# STM32F030F4P6.net
KiCad netlist of a schematic drawn in EAGLE
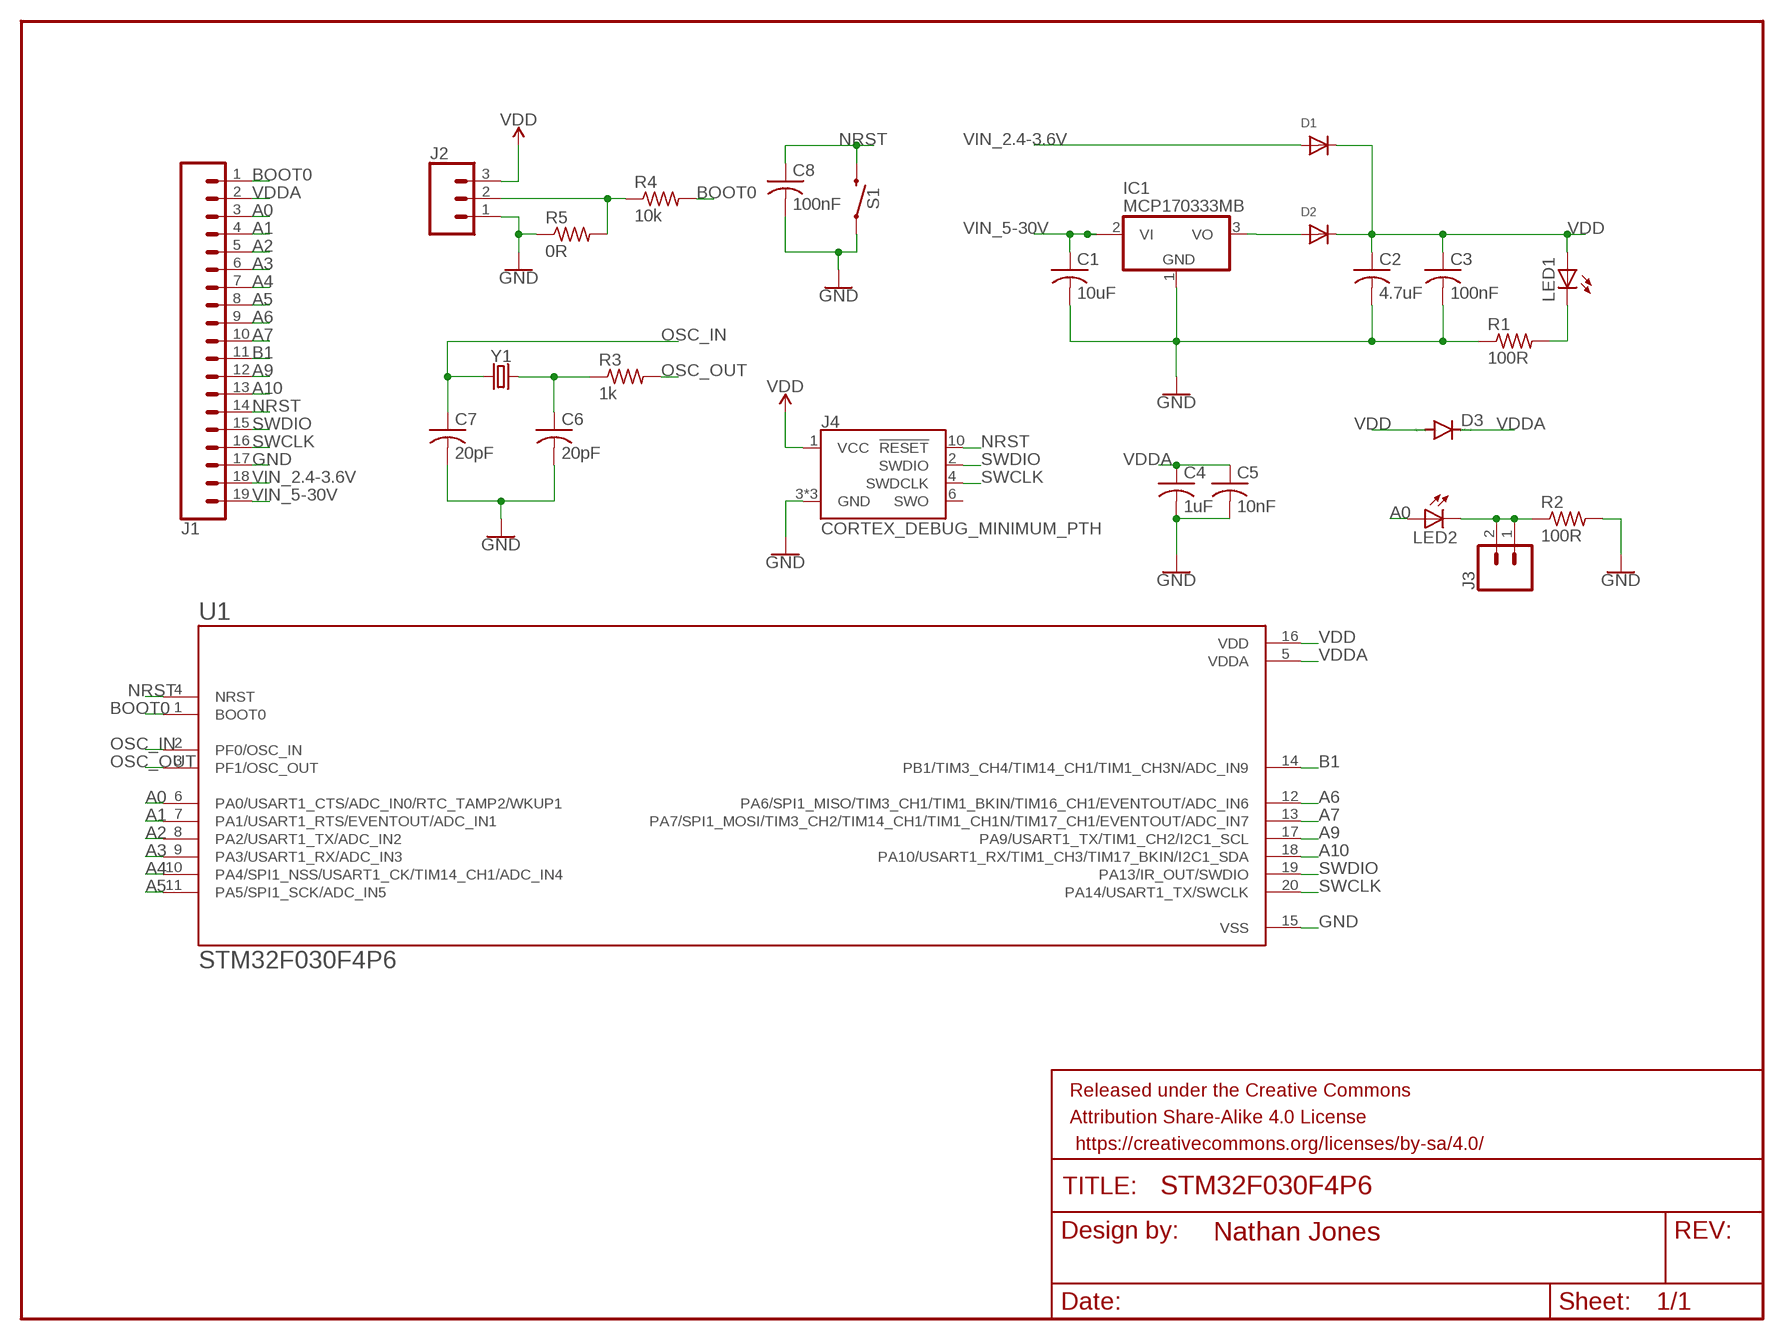
[diagram p0: schematic, sheet 1]

(export (version "E")
  (design (tool "Eeschema 10.0.6"))
  (components
    (comp (ref "C1")
      (value "10uF")
      (footprint "eagle-import:C0603")
      (libsource (lib "eagle-import") (part "C-USC0603"))
    )
    (comp (ref "C2")
      (value "4.7uF")
      (footprint "eagle-import:C0603")
      (libsource (lib "eagle-import") (part "C-USC0603"))
    )
    (comp (ref "C3")
      (value "100nF")
      (footprint "eagle-import:C0603")
      (libsource (lib "eagle-import") (part "C-USC0603"))
    )
    (comp (ref "C4")
      (value "1uF")
      (footprint "eagle-import:C0603")
      (libsource (lib "eagle-import") (part "C-USC0603"))
    )
    (comp (ref "C5")
      (value "10nF")
      (footprint "eagle-import:C0603")
      (libsource (lib "eagle-import") (part "C-USC0603"))
    )
    (comp (ref "C6")
      (value "20pF")
      (footprint "eagle-import:C0603")
      (libsource (lib "eagle-import") (part "C-USC0603"))
    )
    (comp (ref "C7")
      (value "20pF")
      (footprint "eagle-import:C0603")
      (libsource (lib "eagle-import") (part "C-USC0603"))
    )
    (comp (ref "C8")
      (value "100nF")
      (footprint "eagle-import:C0603")
      (libsource (lib "eagle-import") (part "C-USC0603"))
    )
    (comp (ref "D1")
      (value "DIODESOD-123")
      (footprint "eagle-import:SOD-123")
      (libsource (lib "eagle-import") (part "DIODESOD-123"))
    )
    (comp (ref "D2")
      (value "DIODESOD-123")
      (footprint "eagle-import:SOD-123")
      (libsource (lib "eagle-import") (part "DIODESOD-123"))
    )
    (comp (ref "D3")
      (value "DIODE-DO-214AC")
      (footprint "eagle-import:DO-214AC")
      (libsource (lib "eagle-import") (part "DIODE-DO-214AC"))
    )
    (comp (ref "FRAME2")
      (value "FRAME-LETTERNO_PACKAGE")
      (footprint "eagle-import:DUMMY")
      (fields (field (name "DESIGNER") "Nathan Jones") (field (name "DESIGNER_1") "Nathan Jones"))
      (libsource (lib "eagle-import") (part "FRAME-LETTERNO_PACKAGE"))
    )
    (comp (ref "IC1")
      (value "MCP170333MB")
      (footprint "eagle-import:SOT89")
      (libsource (lib "eagle-import") (part "MCP1703MB33"))
    )
    (comp (ref "J1")
      (value "CONN_19")
      (footprint "eagle-import:1X19")
      (libsource (lib "eagle-import") (part "CONN_19"))
    )
    (comp (ref "J2")
      (value "455-1750-1-ND")
      (footprint "eagle-import:1X03")
      (libsource (lib "eagle-import") (part "CONN_03"))
    )
    (comp (ref "J3")
      (value "CONN_02")
      (footprint "eagle-import:1X02")
      (libsource (lib "eagle-import") (part "CONN_02"))
    )
    (comp (ref "J4")
      (value "CORTEX_DEBUG_MINIMUM_PTH")
      (footprint "eagle-import:2X5-PTH-1.27MM")
      (libsource (lib "eagle-import") (part "CORTEX_DEBUG_MINIMUM_PTH"))
    )
    (comp (ref "LED1")
      (value "LEDCHIPLED_0603")
      (footprint "eagle-import:CHIPLED_0603")
      (libsource (lib "eagle-import") (part "LEDCHIPLED_0603"))
    )
    (comp (ref "LED2")
      (value "LEDCHIPLED_0603")
      (footprint "eagle-import:CHIPLED_0603")
      (libsource (lib "eagle-import") (part "LEDCHIPLED_0603"))
    )
    (comp (ref "R1")
      (value "100R")
      (footprint "eagle-import:R0603")
      (libsource (lib "eagle-import") (part "R-US_R0603"))
    )
    (comp (ref "R2")
      (value "100R")
      (footprint "eagle-import:R0603")
      (libsource (lib "eagle-import") (part "R-US_R0603"))
    )
    (comp (ref "R3")
      (value "1k")
      (footprint "eagle-import:R0603")
      (libsource (lib "eagle-import") (part "R-US_R0603"))
    )
    (comp (ref "R4")
      (value "10k")
      (footprint "eagle-import:R0603")
      (libsource (lib "eagle-import") (part "R-US_R0603"))
    )
    (comp (ref "R5")
      (value "0R")
      (footprint "eagle-import:R0603")
      (libsource (lib "eagle-import") (part "R-US_R0603"))
    )
    (comp (ref "S1")
      (value "MOMENTARY-SWITCH-SPST-SMD-5.2-REDUNDANT")
      (footprint "eagle-import:TACTILE_SWITCH_SMD_5.2MM")
      (libsource (lib "eagle-import") (part "MOMENTARY-SWITCH-SPST-SMD-5.2-REDUNDANT"))
    )
    (comp (ref "U1")
      (value "STM32F030F4P6")
      (footprint "eagle-import:SOP65P640X120-20N")
      (fields (field (name "DIGI-KEY_PART_NUMBER") "497-14044-5-ND") (field (name "MF") "STMicroelectronics"))
      (libsource (lib "eagle-import") (part "STM32F030F4P6"))
    )
    (comp (ref "Y1")
      (value "CRYSTALSMD-5X3.2-2PAD")
      (footprint "eagle-import:CRYSTAL-SMD-5X3.2-2PAD")
      (libsource (lib "eagle-import") (part "CRYSTALSMD-5X3.2-2PAD"))
    )
  )
  (nets
    (net (code "1") (name "/A0") (class "Default")
      (node (ref "J1") (pin "3") (pinfunction "3_3") (pintype "passive"))
      (node (ref "LED2") (pin "A") (pinfunction "A_A") (pintype "passive"))
      (node (ref "U1") (pin "6") (pinfunction "PA0/USART1_CTS/ADC_IN0/RTC_TAMP2/WKUP1_6") (pintype "bidirectional"))
    )
    (net (code "2") (name "/A1") (class "Default")
      (node (ref "J1") (pin "4") (pinfunction "4_4") (pintype "passive"))
      (node (ref "U1") (pin "7") (pinfunction "PA1/USART1_RTS/EVENTOUT/ADC_IN1_7") (pintype "bidirectional"))
    )
    (net (code "3") (name "/A2") (class "Default")
      (node (ref "J1") (pin "5") (pinfunction "5_5") (pintype "passive"))
      (node (ref "U1") (pin "8") (pinfunction "PA2/USART1_TX/ADC_IN2_8") (pintype "bidirectional"))
    )
    (net (code "4") (name "/A3") (class "Default")
      (node (ref "J1") (pin "6") (pinfunction "6_6") (pintype "passive"))
      (node (ref "U1") (pin "9") (pinfunction "PA3/USART1_RX/ADC_IN3_9") (pintype "bidirectional"))
    )
    (net (code "5") (name "/A4") (class "Default")
      (node (ref "J1") (pin "7") (pinfunction "7_7") (pintype "passive"))
      (node (ref "U1") (pin "10") (pinfunction "PA4/SPI1_NSS/USART1_CK/TIM14_CH1/ADC_IN4_10") (pintype "bidirectional"))
    )
    (net (code "6") (name "/A5") (class "Default")
      (node (ref "J1") (pin "8") (pinfunction "8_8") (pintype "passive"))
      (node (ref "U1") (pin "11") (pinfunction "PA5/SPI1_SCK/ADC_IN5_11") (pintype "bidirectional"))
    )
    (net (code "7") (name "/A6") (class "Default")
      (node (ref "J1") (pin "9") (pinfunction "9_9") (pintype "passive"))
      (node (ref "U1") (pin "12") (pinfunction "PA6/SPI1_MISO/TIM3_CH1/TIM1_BKIN/TIM16_CH1/EVENTOUT/ADC_IN6_12") (pintype "bidirectional"))
    )
    (net (code "8") (name "/A7") (class "Default")
      (node (ref "J1") (pin "10") (pinfunction "10_10") (pintype "passive"))
      (node (ref "U1") (pin "13") (pinfunction "PA7/SPI1_MOSI/TIM3_CH2/TIM14_CH1/TIM1_CH1N/TIM17_CH1/EVENTOUT/ADC_IN7_13") (pintype "bidirectional"))
    )
    (net (code "9") (name "/A9") (class "Default")
      (node (ref "J1") (pin "12") (pinfunction "12_12") (pintype "passive"))
      (node (ref "U1") (pin "17") (pinfunction "PA9/USART1_TX/TIM1_CH2/I2C1_SCL_17") (pintype "bidirectional"))
    )
    (net (code "10") (name "/A10") (class "Default")
      (node (ref "J1") (pin "13") (pinfunction "13_13") (pintype "passive"))
      (node (ref "U1") (pin "18") (pinfunction "PA10/USART1_RX/TIM1_CH3/TIM17_BKIN/I2C1_SDA_18") (pintype "bidirectional"))
    )
    (net (code "11") (name "/B1") (class "Default")
      (node (ref "J1") (pin "11") (pinfunction "11_11") (pintype "passive"))
      (node (ref "U1") (pin "14") (pinfunction "PB1/TIM3_CH4/TIM14_CH1/TIM1_CH3N/ADC_IN9_14") (pintype "bidirectional"))
    )
    (net (code "12") (name "/BOOT0") (class "Default")
      (node (ref "J1") (pin "1") (pinfunction "1_1") (pintype "passive"))
      (node (ref "R4") (pin "2") (pinfunction "2_2") (pintype "passive"))
      (node (ref "U1") (pin "1") (pinfunction "BOOT0_1") (pintype "input"))
    )
    (net (code "13") (name "/NRST") (class "Default")
      (node (ref "C8") (pin "1") (pinfunction "1_1") (pintype "passive"))
      (node (ref "J1") (pin "14") (pinfunction "14_14") (pintype "passive"))
      (node (ref "J4") (pin "10") (pinfunction "~{RESET}_10") (pintype "bidirectional"))
      (node (ref "S1") (pin "3") (pinfunction "2_3") (pintype "passive"))
      (node (ref "S1") (pin "4") (pinfunction "2_4") (pintype "passive"))
      (node (ref "U1") (pin "4") (pinfunction "NRST_4") (pintype "bidirectional"))
    )
    (net (code "14") (name "/OSC_IN") (class "Default")
      (node (ref "C7") (pin "1") (pinfunction "1_1") (pintype "passive"))
      (node (ref "U1") (pin "2") (pinfunction "PF0/OSC_IN_2") (pintype "bidirectional"))
      (node (ref "Y1") (pin "P$2") (pinfunction "2_P$2") (pintype "passive"))
    )
    (net (code "15") (name "/OSC_OUT") (class "Default")
      (node (ref "R3") (pin "2") (pinfunction "2_2") (pintype "passive"))
      (node (ref "U1") (pin "3") (pinfunction "PF1/OSC_OUT_3") (pintype "bidirectional"))
    )
    (net (code "16") (name "/SWCLK") (class "Default")
      (node (ref "J1") (pin "16") (pinfunction "16_16") (pintype "passive"))
      (node (ref "J4") (pin "4") (pinfunction "SWDCLK_4") (pintype "bidirectional"))
      (node (ref "U1") (pin "20") (pinfunction "PA14/USART1_TX/SWCLK_20") (pintype "bidirectional"))
    )
    (net (code "17") (name "/SWDIO") (class "Default")
      (node (ref "J1") (pin "15") (pinfunction "15_15") (pintype "passive"))
      (node (ref "J4") (pin "2") (pinfunction "SWDIO_2") (pintype "bidirectional"))
      (node (ref "U1") (pin "19") (pinfunction "PA13/IR_OUT/SWDIO_19") (pintype "bidirectional"))
    )
    (net (code "18") (name "/VDDA") (class "Default")
      (node (ref "C4") (pin "1") (pinfunction "1_1") (pintype "passive"))
      (node (ref "C5") (pin "1") (pinfunction "1_1") (pintype "passive"))
      (node (ref "D3") (pin "C") (pinfunction "C_C") (pintype "passive"))
      (node (ref "J1") (pin "2") (pinfunction "2_2") (pintype "passive"))
      (node (ref "U1") (pin "5") (pinfunction "VDDA_5") (pintype "power_in"))
    )
    (net (code "19") (name "/VIN_2.4-3.6V") (class "Default")
      (node (ref "D1") (pin "A") (pinfunction "A_A") (pintype "passive"))
      (node (ref "J1") (pin "18") (pinfunction "18_18") (pintype "passive"))
    )
    (net (code "20") (name "/VIN_5-30V") (class "Default")
      (node (ref "C1") (pin "1") (pinfunction "1_1") (pintype "passive"))
      (node (ref "IC1") (pin "2@1") (pinfunction "VI1_2@1") (pintype "input"))
      (node (ref "J1") (pin "19") (pinfunction "19_19") (pintype "passive"))
    )
    (net (code "21") (name "GND") (class "Default")
      (node (ref "C1") (pin "2") (pinfunction "2_2") (pintype "passive"))
      (node (ref "C2") (pin "2") (pinfunction "2_2") (pintype "passive"))
      (node (ref "C3") (pin "2") (pinfunction "2_2") (pintype "passive"))
      (node (ref "C4") (pin "2") (pinfunction "2_2") (pintype "passive"))
      (node (ref "C5") (pin "2") (pinfunction "2_2") (pintype "passive"))
      (node (ref "C6") (pin "2") (pinfunction "2_2") (pintype "passive"))
      (node (ref "C7") (pin "2") (pinfunction "2_2") (pintype "passive"))
      (node (ref "C8") (pin "2") (pinfunction "2_2") (pintype "passive"))
      (node (ref "IC1") (pin "1") (pinfunction "GND_1") (pintype "passive"))
      (node (ref "J1") (pin "17") (pinfunction "17_17") (pintype "passive"))
      (node (ref "J2") (pin "1") (pinfunction "1_1") (pintype "passive"))
      (node (ref "J4") (pin "3") (pinfunction "GND_3") (pintype "bidirectional"))
      (node (ref "J4") (pin "5") (pinfunction "GND_5") (pintype "bidirectional"))
      (node (ref "J4") (pin "9") (pinfunction "GND_9") (pintype "bidirectional"))
      (node (ref "R1") (pin "1") (pinfunction "1_1") (pintype "passive"))
      (node (ref "R2") (pin "2") (pinfunction "2_2") (pintype "passive"))
      (node (ref "R5") (pin "1") (pinfunction "1_1") (pintype "passive"))
      (node (ref "S1") (pin "1") (pinfunction "1_1") (pintype "passive"))
      (node (ref "S1") (pin "2") (pinfunction "1_2") (pintype "passive"))
      (node (ref "U1") (pin "15") (pinfunction "VSS_15") (pintype "power_in"))
    )
    (net (code "22") (name "Net-(IC1-VO)") (class "Default")
      (node (ref "D2") (pin "A") (pinfunction "A_A") (pintype "passive"))
      (node (ref "IC1") (pin "3") (pinfunction "VO_3") (pintype "passive"))
    )
    (net (code "23") (name "Net-(J2-Pad2)") (class "Default")
      (node (ref "J2") (pin "2") (pinfunction "2_2") (pintype "passive"))
      (node (ref "R4") (pin "1") (pinfunction "1_1") (pintype "passive"))
      (node (ref "R5") (pin "2") (pinfunction "2_2") (pintype "passive"))
    )
    (net (code "24") (name "Net-(J3-Pad1)") (class "Default")
      (node (ref "J3") (pin "1") (pinfunction "1_1") (pintype "passive"))
      (node (ref "J3") (pin "2") (pinfunction "2_2") (pintype "passive"))
      (node (ref "LED2") (pin "C") (pinfunction "C_C") (pintype "passive"))
      (node (ref "R2") (pin "1") (pinfunction "1_1") (pintype "passive"))
    )
    (net (code "25") (name "Net-(LED1-PadC)") (class "Default")
      (node (ref "LED1") (pin "C") (pinfunction "C_C") (pintype "passive"))
      (node (ref "R1") (pin "2") (pinfunction "2_2") (pintype "passive"))
    )
    (net (code "26") (name "Net-(Y1-1)") (class "Default")
      (node (ref "C6") (pin "1") (pinfunction "1_1") (pintype "passive"))
      (node (ref "R3") (pin "1") (pinfunction "1_1") (pintype "passive"))
      (node (ref "Y1") (pin "P$1") (pinfunction "1_P$1") (pintype "passive"))
    )
    (net (code "27") (name "VDD") (class "Default")
      (node (ref "C2") (pin "1") (pinfunction "1_1") (pintype "passive"))
      (node (ref "C3") (pin "1") (pinfunction "1_1") (pintype "passive"))
      (node (ref "D1") (pin "C") (pinfunction "C_C") (pintype "passive"))
      (node (ref "D2") (pin "C") (pinfunction "C_C") (pintype "passive"))
      (node (ref "D3") (pin "A") (pinfunction "A_A") (pintype "passive"))
      (node (ref "J2") (pin "3") (pinfunction "3_3") (pintype "passive"))
      (node (ref "J4") (pin "1") (pinfunction "VCC_1") (pintype "bidirectional"))
      (node (ref "LED1") (pin "A") (pinfunction "A_A") (pintype "passive"))
      (node (ref "U1") (pin "16") (pinfunction "VDD_16") (pintype "power_in"))
    )
    (net (code "28") (name "unconnected-(IC1-VI-Pad2)") (class "Default")
      (node (ref "IC1") (pin "2") (pinfunction "VI_2") (pintype "input"))
    )
    (net (code "29") (name "unconnected-(J4-SWO-Pad6)") (class "Default")
      (node (ref "J4") (pin "6") (pinfunction "SWO_6") (pintype "bidirectional"))
    )
  )
)
